# MouseBox_PortBreakout_r1.net
KiCad netlist of a schematic drawn in EAGLE
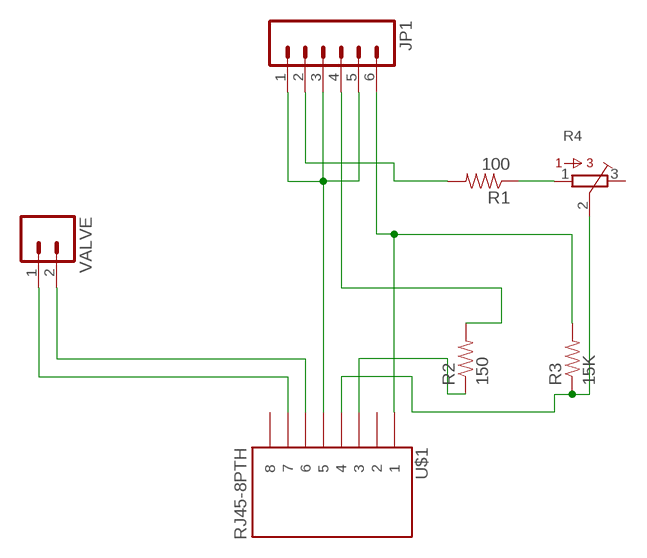
[diagram p0: schematic, sheet 1]

(export (version "E")
  (design (tool "Eeschema 10.0.6"))
  (components
    (comp (ref "JP1")
      (value "M063.5MM-6")
      (footprint "eagle-import:SCREWTERMINAL-3.5MM-6")
      (libsource (lib "eagle-import") (part "M063.5MM-6"))
    )
    (comp (ref "R1")
      (value "100")
      (footprint "eagle-import:AXIAL-0.3")
      (libsource (lib "eagle-import") (part "RESISTORAXIAL-0.3"))
    )
    (comp (ref "R2")
      (value "150")
      (footprint "eagle-import:AXIAL-0.3")
      (libsource (lib "eagle-import") (part "RESISTORAXIAL-0.3"))
    )
    (comp (ref "R3")
      (value "15K")
      (footprint "eagle-import:AXIAL-0.3")
      (libsource (lib "eagle-import") (part "RESISTORAXIAL-0.3"))
    )
    (comp (ref "R4")
      (value "3362R")
      (footprint "eagle-import:3362R")
      (libsource (lib "eagle-import") (part "3362R"))
    )
    (comp (ref "U$1")
      (value "RJ45-8PTH")
      (footprint "eagle-import:RJ45-8")
      (libsource (lib "eagle-import") (part "RJ45-8PTH"))
    )
    (comp (ref "VALVE")
      (value "M023.5MM_LOCK")
      (footprint "eagle-import:SCREWTERMINAL-3.5MM-2_LOCK")
      (libsource (lib "eagle-import") (part "M023.5MM_LOCK"))
    )
  )
  (nets
    (net (code "1") (name "Net-(JP1-Pad1)") (class "Default")
      (node (ref "JP1") (pin "1") (pinfunction "1_1") (pintype "passive"))
      (node (ref "JP1") (pin "3") (pinfunction "3_3") (pintype "passive"))
      (node (ref "JP1") (pin "5") (pinfunction "5_5") (pintype "passive"))
      (node (ref "U$1") (pin "5") (pinfunction "5_5") (pintype "bidirectional"))
    )
    (net (code "2") (name "Net-(R1-1)") (class "Default")
      (node (ref "R1") (pin "P$1") (pinfunction "1_P$1") (pintype "passive"))
      (node (ref "R4") (pin "1") (pinfunction "1_1") (pintype "passive"))
    )
    (net (code "3") (name "Net-(R1-2)") (class "Default")
      (node (ref "JP1") (pin "2") (pinfunction "2_2") (pintype "passive"))
      (node (ref "R1") (pin "P$2") (pinfunction "2_P$2") (pintype "passive"))
    )
    (net (code "4") (name "Net-(R2-1)") (class "Default")
      (node (ref "R2") (pin "P$1") (pinfunction "1_P$1") (pintype "passive"))
      (node (ref "U$1") (pin "3") (pinfunction "3_3") (pintype "bidirectional"))
    )
    (net (code "5") (name "Net-(R2-2)") (class "Default")
      (node (ref "JP1") (pin "4") (pinfunction "4_4") (pintype "passive"))
      (node (ref "R2") (pin "P$2") (pinfunction "2_P$2") (pintype "passive"))
    )
    (net (code "6") (name "Net-(R3-1)") (class "Default")
      (node (ref "R3") (pin "P$1") (pinfunction "1_P$1") (pintype "passive"))
      (node (ref "R4") (pin "2") (pinfunction "2_2") (pintype "passive"))
      (node (ref "U$1") (pin "4") (pinfunction "4_4") (pintype "bidirectional"))
    )
    (net (code "7") (name "Net-(R3-2)") (class "Default")
      (node (ref "JP1") (pin "6") (pinfunction "6_6") (pintype "passive"))
      (node (ref "R3") (pin "P$2") (pinfunction "2_P$2") (pintype "passive"))
      (node (ref "U$1") (pin "1") (pinfunction "1_1") (pintype "bidirectional"))
    )
    (net (code "8") (name "Net-(U$1-Pad6)") (class "Default")
      (node (ref "U$1") (pin "6") (pinfunction "6_6") (pintype "bidirectional"))
      (node (ref "VALVE") (pin "2") (pinfunction "2_2") (pintype "passive"))
    )
    (net (code "9") (name "Net-(U$1-Pad7)") (class "Default")
      (node (ref "U$1") (pin "7") (pinfunction "7_7") (pintype "bidirectional"))
      (node (ref "VALVE") (pin "1") (pinfunction "1_1") (pintype "passive"))
    )
    (net (code "10") (name "unconnected-(R4-Pad3)") (class "Default")
      (node (ref "R4") (pin "3") (pinfunction "3_3") (pintype "passive"))
    )
    (net (code "11") (name "unconnected-(U$1-Pad2)") (class "Default")
      (node (ref "U$1") (pin "2") (pinfunction "2_2") (pintype "bidirectional"))
    )
    (net (code "12") (name "unconnected-(U$1-Pad8)") (class "Default")
      (node (ref "U$1") (pin "8") (pinfunction "8_8") (pintype "bidirectional"))
    )
  )
)
